# Power_Supply.net
KiCad netlist of a schematic drawn in Altium Designer
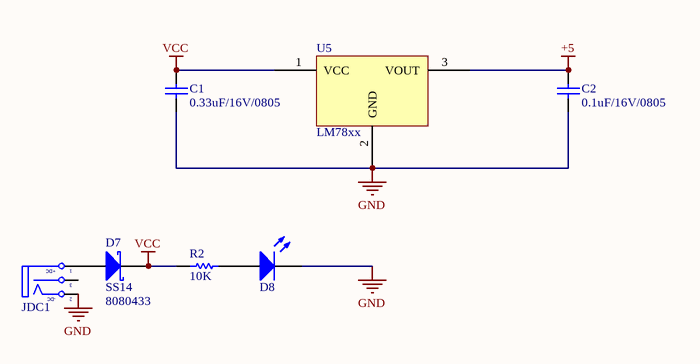
[diagram p0: Power_Supply.SchDoc]

(export (version "E")
  (design (tool "Eeschema 10.0.6"))
  (components
    (comp (ref "C1")
      (value "0.33uF/16V/0805")
      (footprint "CAP-SM-0805")
      (description "Capacitor")
      (fields (field (name "Comment") "Cap Non-Pol SMD"))
      (libsource (lib "PIF_Library") (part "Cap Non-Pol SMD"))
    )
    (comp (ref "C2")
      (value "0.1uF/16V/0805")
      (footprint "CAP-SM-0805")
      (description "Capacitor")
      (fields (field (name "Comment") "Cap Non-Pol SMD"))
      (libsource (lib "PIF_Library") (part "Cap Non-Pol SMD"))
    )
    (comp (ref "D7")
      (value "D Schottky")
      (footprint "SS34")
      (description "Schottky Diode")
      (fields
        (field (name "SUPPLIER PART NUMBER 1") "SS14")
        (field (name "SUPPLIER PART NUMBER 2") "8080433")
        (field (name "PUBLISHER") "Altium Limited")
      )
      (libsource (lib "PIF_Library") (part "D Schottky"))
    )
    (comp (ref "D8")
      (value "LED SMD")
      (footprint "LED_0805_Blue")
      (description "LED")
      (libsource (lib "PIF_Library") (part "LED SMD"))
    )
    (comp (ref "JDC1")
      (value "Jack DC")
      (footprint "DC-IN")
      (description "Jack DC input")
      (libsource (lib "PIF_Library") (part "Jack DC"))
    )
    (comp (ref "R2")
      (value "10K")
      (footprint "RES-SM-0805")
      (description "Resistor")
      (fields (field (name "Comment") "RESISTOR SMD"))
      (libsource (lib "PIF_Library") (part "RESISTOR SMD"))
    )
    (comp (ref "U5")
      (value "LM78xx")
      (footprint "DPAK228P1014X239-3N")
      (libsource (lib "MiclsLib") (part "LM78xx"))
    )
  )
  (nets
    (net (code "1") (name "+5") (class "Default")
      (node (ref "C2") (pin "2") (pinfunction "2_2") (pintype "passive"))
      (node (ref "U5") (pin "3") (pinfunction "VOUT_3") (pintype "passive"))
    )
    (net (code "2") (name "GND") (class "Default")
      (node (ref "C1") (pin "1") (pinfunction "1_1") (pintype "passive"))
      (node (ref "C2") (pin "1") (pinfunction "1_1") (pintype "passive"))
      (node (ref "D8") (pin "2") (pinfunction "K_2") (pintype "passive"))
      (node (ref "JDC1") (pin "2") (pinfunction "TN_2") (pintype "passive"))
      (node (ref "U5") (pin "2") (pinfunction "GND_2") (pintype "passive"))
    )
    (net (code "3") (name "Net-(D8-A)") (class "Default")
      (node (ref "D8") (pin "1") (pinfunction "A_1") (pintype "passive"))
      (node (ref "R2") (pin "2") (pinfunction "2_2") (pintype "passive"))
    )
    (net (code "4") (name "Net-(JDC1-T)") (class "Default")
      (node (ref "D7") (pin "A") (pinfunction "A_A") (pintype "passive"))
      (node (ref "JDC1") (pin "1") (pinfunction "T_1") (pintype "passive"))
    )
    (net (code "5") (name "VCC") (class "Default")
      (node (ref "C1") (pin "2") (pinfunction "2_2") (pintype "passive"))
      (node (ref "D7") (pin "K") (pinfunction "K_K") (pintype "passive"))
      (node (ref "R2") (pin "1") (pinfunction "1_1") (pintype "passive"))
      (node (ref "U5") (pin "1") (pinfunction "VCC_1") (pintype "passive"))
    )
    (net (code "6") (name "unconnected-(JDC1-S-Pad3)") (class "Default")
      (node (ref "JDC1") (pin "3") (pinfunction "S_3") (pintype "power_in"))
    )
  )
)
